# MiniClock.net
KiCad netlist of a schematic drawn in Altium Designer
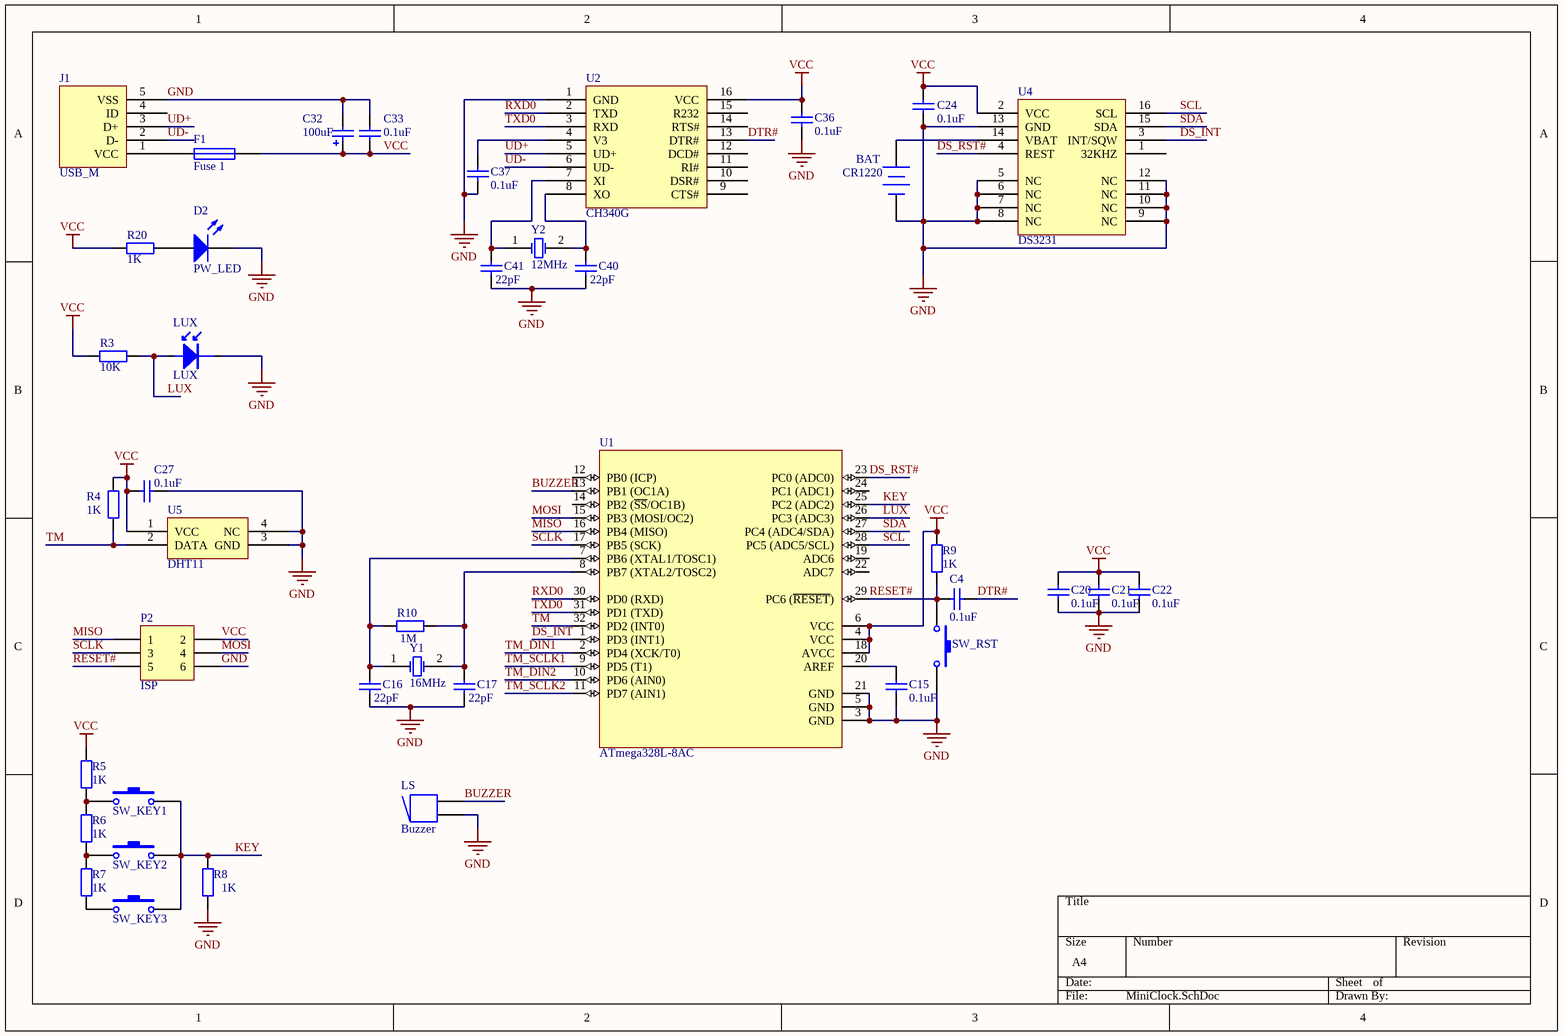
[diagram p0: MiniClock.SchDoc]

(export (version "E")
  (design (tool "Eeschema 10.0.6"))
  (components
    (comp (ref "BAT")
      (value "CR1220")
      (footprint "CR1220")
      (description "Multicell Battery")
      (fields (field (name "PUBLISHER") "Altium Limited"))
      (libsource (lib "Miscellaneous Devices") (part "Battery"))
    )
    (comp (ref "C4")
      (value "0.1uF")
      (footprint "C-0805")
      (description "Capacitor")
      (fields (field (name "Comment") "Cap") (field (name "PUBLISHER") "Altium Limited"))
      (libsource (lib "Miscellaneous Devices") (part "Cap"))
    )
    (comp (ref "C15")
      (value "0.1uF")
      (footprint "C-0805")
      (description "Capacitor")
      (fields (field (name "Comment") "Cap") (field (name "PUBLISHER") "Altium Limited"))
      (libsource (lib "Miscellaneous Devices") (part "Cap"))
    )
    (comp (ref "C16")
      (value "22pF")
      (footprint "C-0805")
      (description "Capacitor")
      (fields (field (name "Comment") "Cap") (field (name "PUBLISHER") "Altium Limited"))
      (libsource (lib "Miscellaneous Devices") (part "Cap"))
    )
    (comp (ref "C17")
      (value "22pF")
      (footprint "C-0805")
      (description "Capacitor")
      (fields (field (name "Comment") "Cap") (field (name "PUBLISHER") "Altium Limited"))
      (libsource (lib "Miscellaneous Devices") (part "Cap"))
    )
    (comp (ref "C20")
      (value "0.1uF")
      (footprint "C-0805")
      (description "Capacitor")
      (fields (field (name "Comment") "Cap") (field (name "PUBLISHER") "Altium Limited"))
      (libsource (lib "Miscellaneous Devices") (part "Cap"))
    )
    (comp (ref "C21")
      (value "0.1uF")
      (footprint "C-0805")
      (description "Capacitor")
      (fields (field (name "Comment") "Cap") (field (name "PUBLISHER") "Altium Limited"))
      (libsource (lib "Miscellaneous Devices") (part "Cap"))
    )
    (comp (ref "C22")
      (value "0.1uF")
      (footprint "C-0805")
      (description "Capacitor")
      (fields (field (name "Comment") "Cap") (field (name "PUBLISHER") "Altium Limited"))
      (libsource (lib "Miscellaneous Devices") (part "Cap"))
    )
    (comp (ref "C24")
      (value "0.1uF")
      (footprint "C-0805")
      (description "Capacitor")
      (fields (field (name "Comment") "Cap") (field (name "PUBLISHER") "Altium Limited"))
      (libsource (lib "Miscellaneous Devices") (part "Cap"))
    )
    (comp (ref "C27")
      (value "0.1uF")
      (footprint "C-0805")
      (description "Capacitor")
      (fields (field (name "Comment") "Cap") (field (name "PUBLISHER") "Altium Limited"))
      (libsource (lib "Miscellaneous Devices") (part "Cap"))
    )
    (comp (ref "C32")
      (value "100uF")
      (footprint "CAP-3528")
      (description "Polarized Capacitor (Axial)")
      (fields (field (name "Comment") "Cap Pol2") (field (name "PUBLISHER") "Altium Limited"))
      (libsource (lib "Miscellaneous Devices") (part "Cap Pol2"))
    )
    (comp (ref "C33")
      (value "0.1uF")
      (footprint "C-0805")
      (description "Capacitor")
      (fields (field (name "Comment") "Cap") (field (name "PUBLISHER") "Altium Limited"))
      (libsource (lib "Miscellaneous Devices") (part "Cap"))
    )
    (comp (ref "C36")
      (value "0.1uF")
      (footprint "C-0805")
      (description "Capacitor")
      (fields (field (name "Comment") "Cap") (field (name "PUBLISHER") "Altium Limited"))
      (libsource (lib "Miscellaneous Devices") (part "Cap"))
    )
    (comp (ref "C37")
      (value "0.1uF")
      (footprint "C-0805")
      (description "Capacitor")
      (fields (field (name "Comment") "Cap") (field (name "PUBLISHER") "Altium Limited"))
      (libsource (lib "Miscellaneous Devices") (part "Cap"))
    )
    (comp (ref "C40")
      (value "22pF")
      (footprint "C-0805")
      (description "Capacitor")
      (fields (field (name "Comment") "Cap") (field (name "PUBLISHER") "Altium Limited"))
      (libsource (lib "Miscellaneous Devices") (part "Cap"))
    )
    (comp (ref "C41")
      (value "22pF")
      (footprint "C-0805")
      (description "Capacitor")
      (fields (field (name "Comment") "Cap") (field (name "PUBLISHER") "Altium Limited"))
      (libsource (lib "Miscellaneous Devices") (part "Cap"))
    )
    (comp (ref "D2")
      (value "PW_LED")
      (footprint "LED-0805")
      (description "Typical RED, GREEN, YELLOW, AMBER GaAs LED")
      (fields (field (name "PUBLISHER") "Altium Limited"))
      (libsource (lib "Miscellaneous Devices") (part "LED2"))
    )
    (comp (ref "F1")
      (value "Fuse 1")
      (footprint "0805-1")
      (description "Fuse")
      (fields (field (name "PUBLISHER") "Altium Limited"))
      (libsource (lib "Miscellaneous Devices") (part "Fuse 1"))
    )
    (comp (ref "J1")
      (value "USB_M")
      (footprint "USB_MICRO_5S_B")
      (description "Micro/Mini USB")
      (libsource (lib "HDR_Fszhang") (part "USB_M"))
    )
    (comp (ref "LS")
      (value "Buzzer")
      (footprint "BEEP-S")
      (description "Magnetic Transducer Buzzer")
      (fields (field (name "PUBLISHER") "Altium Limited"))
      (libsource (lib "Miscellaneous Devices") (part "Buzzer"))
    )
    (comp (ref "LUX") (value "LUX") (footprint "AX_2.54") (libsource (lib "Schlib1") (part "LUX")))
    (comp (ref "P2")
      (value "ISP")
      (footprint "HDR2X3")
      (description "Header, 3-Pin, Dual row")
      (fields (field (name "PUBLISHER") "Altium Limited"))
      (libsource (lib "Miscellaneous Connectors") (part "Header 3X2"))
    )
    (comp (ref "R3")
      (value "10K")
      (footprint "0805-1")
      (description "Resistor")
      (fields (field (name "Comment") "Res2") (field (name "PUBLISHER") "Altium Limited"))
      (libsource (lib "") (part "Res2_3"))
    )
    (comp (ref "R4")
      (value "1K")
      (footprint "0805-1")
      (description "Resistor")
      (fields (field (name "Comment") "Res2") (field (name "PUBLISHER") "Altium Limited"))
      (libsource (lib "Miscellaneous Devices") (part "Res2"))
    )
    (comp (ref "R5")
      (value "1K")
      (footprint "0805-1")
      (description "Resistor")
      (fields (field (name "Comment") "Res2") (field (name "PUBLISHER") "Altium Limited"))
      (libsource (lib "Miscellaneous Devices") (part "Res2"))
    )
    (comp (ref "R6")
      (value "1K")
      (footprint "0805-1")
      (description "Resistor")
      (fields (field (name "Comment") "Res2") (field (name "PUBLISHER") "Altium Limited"))
      (libsource (lib "Miscellaneous Devices") (part "Res2"))
    )
    (comp (ref "R7")
      (value "1K")
      (footprint "0805-1")
      (description "Resistor")
      (fields (field (name "Comment") "Res2") (field (name "PUBLISHER") "Altium Limited"))
      (libsource (lib "Miscellaneous Devices") (part "Res2"))
    )
    (comp (ref "R8")
      (value "1K")
      (footprint "0805-1")
      (description "Resistor")
      (fields (field (name "Comment") "Res2") (field (name "PUBLISHER") "Altium Limited"))
      (libsource (lib "") (part "Res2_2"))
    )
    (comp (ref "R9")
      (value "1K")
      (footprint "0805-1")
      (description "Resistor")
      (fields (field (name "Comment") "Res2") (field (name "PUBLISHER") "Altium Limited"))
      (libsource (lib "Miscellaneous Devices") (part "Res2"))
    )
    (comp (ref "R10")
      (value "1M")
      (footprint "0805-1")
      (description "Resistor")
      (fields (field (name "Comment") "Res2") (field (name "PUBLISHER") "Altium Limited"))
      (libsource (lib "") (part "Res2_1"))
    )
    (comp (ref "R20")
      (value "1K")
      (footprint "0805-1")
      (description "Resistor")
      (fields (field (name "Comment") "Res2") (field (name "PUBLISHER") "Altium Limited"))
      (libsource (lib "") (part "Res2_3"))
    )
    (comp (ref "SW_KEY1")
      (value "SW-PB")
      (footprint "SW_PB2_A1")
      (description "Switch")
      (fields (field (name "PUBLISHER") "Altium Limited"))
      (libsource (lib "Miscellaneous Devices") (part "SW-PB"))
    )
    (comp (ref "SW_KEY2")
      (value "SW-PB")
      (footprint "SW_PB2_A1")
      (description "Switch")
      (fields (field (name "PUBLISHER") "Altium Limited"))
      (libsource (lib "Miscellaneous Devices") (part "SW-PB"))
    )
    (comp (ref "SW_KEY3")
      (value "SW-PB")
      (footprint "SW_PB2_A1")
      (description "Switch")
      (fields (field (name "PUBLISHER") "Altium Limited"))
      (libsource (lib "Miscellaneous Devices") (part "SW-PB"))
    )
    (comp (ref "SW_RST")
      (value "SW-PB")
      (footprint "SW_PB2_A1")
      (description "Switch")
      (fields (field (name "PUBLISHER") "Altium Limited"))
      (libsource (lib "Miscellaneous Devices") (part "SW-PB"))
    )
    (comp (ref "U1")
      (value "ATmega328L-8AC")
      (footprint "32A_M")
      (description "8-Bit AVR Microcontroller with 8K Bytes of In-System Programmable Flash Memory")
      (fields (field (name "PUBLISHER") "Altium Limited"))
      (libsource (lib "Atmel Microcontroller 8-Bit AVR") (part "ATmega8L-8AC"))
    )
    (comp (ref "U2") (value "CH340G") (footprint "SOIC-16") (libsource (lib "Schlib1") (part "CH340G")))
    (comp (ref "U4") (value "DS3231") (footprint "SOIC-16W") (libsource (lib "Schlib1") (part "DS3231")))
    (comp (ref "U5") (value "DHT11") (footprint "DHTxx_simple") (libsource (lib "Schlib1") (part "DHT22")))
    (comp (ref "Y1")
      (value "16MHz")
      (footprint "X-SM49")
      (description "Crystal Oscillator")
      (fields (field (name "PUBLISHER") "Altium Limited"))
      (libsource (lib "Miscellaneous Devices") (part "XTAL"))
    )
    (comp (ref "Y2")
      (value "12MHz")
      (footprint "X-SM49")
      (description "Crystal Oscillator")
      (fields (field (name "PUBLISHER") "Altium Limited"))
      (libsource (lib "Miscellaneous Devices") (part "XTAL"))
    )
  )
  (nets
    (net (code "1") (name "/BUZZER") (class "Default")
      (node (ref "LS") (pin "2") (pinfunction "2_2") (pintype "passive"))
      (node (ref "U1") (pin "13") (pinfunction "PB1_(OC1A)_13") (pintype "bidirectional"))
    )
    (net (code "2") (name "/DS_INT") (class "Default")
      (node (ref "U1") (pin "1") (pinfunction "PD3_(INT1)_1") (pintype "bidirectional"))
      (node (ref "U4") (pin "3") (pinfunction "INT/SQW_3") (pintype "passive"))
    )
    (net (code "3") (name "/DS_RST#") (class "Default")
      (node (ref "U1") (pin "23") (pinfunction "PC0_(ADC0)_23") (pintype "bidirectional"))
      (node (ref "U4") (pin "4") (pinfunction "REST_4") (pintype "passive"))
    )
    (net (code "4") (name "/DTR#") (class "Default")
      (node (ref "C4") (pin "2") (pinfunction "2_2") (pintype "passive"))
      (node (ref "U2") (pin "13") (pinfunction "DTR#_13") (pintype "passive"))
    )
    (net (code "5") (name "/KEY") (class "Default")
      (node (ref "R8") (pin "1") (pinfunction "1_1") (pintype "passive"))
      (node (ref "SW_KEY1") (pin "2") (pinfunction "2_2") (pintype "passive"))
      (node (ref "SW_KEY2") (pin "2") (pinfunction "2_2") (pintype "passive"))
      (node (ref "SW_KEY3") (pin "2") (pinfunction "2_2") (pintype "passive"))
      (node (ref "U1") (pin "25") (pinfunction "PC2_(ADC2)_25") (pintype "bidirectional"))
    )
    (net (code "6") (name "/LUX") (class "Default")
      (node (ref "LUX") (pin "1") (pinfunction "1_1") (pintype "passive"))
      (node (ref "R3") (pin "1") (pinfunction "1_1") (pintype "passive"))
      (node (ref "U1") (pin "26") (pinfunction "PC3_(ADC3)_26") (pintype "bidirectional"))
    )
    (net (code "7") (name "/MISO") (class "Default")
      (node (ref "P2") (pin "1") (pinfunction "1_1") (pintype "passive"))
      (node (ref "U1") (pin "16") (pinfunction "PB4_(MISO)_16") (pintype "bidirectional"))
    )
    (net (code "8") (name "/MOSI") (class "Default")
      (node (ref "P2") (pin "4") (pinfunction "4_4") (pintype "passive"))
      (node (ref "U1") (pin "15") (pinfunction "PB3_(MOSI/OC2)_15") (pintype "bidirectional"))
    )
    (net (code "9") (name "/RESET#") (class "Default")
      (node (ref "C4") (pin "1") (pinfunction "1_1") (pintype "passive"))
      (node (ref "P2") (pin "5") (pinfunction "5_5") (pintype "passive"))
      (node (ref "R9") (pin "1") (pinfunction "1_1") (pintype "passive"))
      (node (ref "SW_RST") (pin "1") (pinfunction "1_1") (pintype "passive"))
      (node (ref "U1") (pin "29") (pinfunction "PC6_(~{RESET})_29") (pintype "bidirectional"))
    )
    (net (code "10") (name "/RXD0") (class "Default")
      (node (ref "U1") (pin "30") (pinfunction "PD0_(RXD)_30") (pintype "bidirectional"))
      (node (ref "U2") (pin "2") (pinfunction "TXD_2") (pintype "passive"))
    )
    (net (code "11") (name "/SCL") (class "Default")
      (node (ref "U1") (pin "28") (pinfunction "PC5_(ADC5/SCL)_28") (pintype "bidirectional"))
      (node (ref "U4") (pin "16") (pinfunction "SCL_16") (pintype "passive"))
    )
    (net (code "12") (name "/SCLK") (class "Default")
      (node (ref "P2") (pin "3") (pinfunction "3_3") (pintype "passive"))
      (node (ref "U1") (pin "17") (pinfunction "PB5_(SCK)_17") (pintype "bidirectional"))
    )
    (net (code "13") (name "/SDA") (class "Default")
      (node (ref "U1") (pin "27") (pinfunction "PC4_(ADC4/SDA)_27") (pintype "bidirectional"))
      (node (ref "U4") (pin "15") (pinfunction "SDA_15") (pintype "passive"))
    )
    (net (code "14") (name "/TM") (class "Default")
      (node (ref "R4") (pin "1") (pinfunction "1_1") (pintype "passive"))
      (node (ref "U1") (pin "32") (pinfunction "PD2_(INT0)_32") (pintype "bidirectional"))
      (node (ref "U5") (pin "2") (pinfunction "DATA_2") (pintype "passive"))
    )
    (net (code "15") (name "/TM_DIN1") (class "Default")
      (node (ref "U1") (pin "2") (pinfunction "PD4_(XCK/T0)_2") (pintype "bidirectional"))
    )
    (net (code "16") (name "/TM_DIN2") (class "Default")
      (node (ref "U1") (pin "10") (pinfunction "PD6_(AIN0)_10") (pintype "bidirectional"))
    )
    (net (code "17") (name "/TM_SCLK1") (class "Default")
      (node (ref "U1") (pin "9") (pinfunction "PD5_(T1)_9") (pintype "bidirectional"))
    )
    (net (code "18") (name "/TM_SCLK2") (class "Default")
      (node (ref "U1") (pin "11") (pinfunction "PD7_(AIN1)_11") (pintype "bidirectional"))
    )
    (net (code "19") (name "/TXD0") (class "Default")
      (node (ref "U1") (pin "31") (pinfunction "PD1_(TXD)_31") (pintype "bidirectional"))
      (node (ref "U2") (pin "3") (pinfunction "RXD_3") (pintype "passive"))
    )
    (net (code "20") (name "/UD+") (class "Default")
      (node (ref "J1") (pin "3") (pinfunction "D+_3") (pintype "passive"))
      (node (ref "U2") (pin "5") (pinfunction "UD+_5") (pintype "passive"))
    )
    (net (code "21") (name "/UD-") (class "Default")
      (node (ref "J1") (pin "2") (pinfunction "D-_2") (pintype "passive"))
      (node (ref "U2") (pin "6") (pinfunction "UD-_6") (pintype "passive"))
    )
    (net (code "22") (name "GND") (class "Default")
      (node (ref "BAT") (pin "2") (pinfunction "-_2") (pintype "passive"))
      (node (ref "C15") (pin "1") (pinfunction "1_1") (pintype "passive"))
      (node (ref "C16") (pin "1") (pinfunction "1_1") (pintype "passive"))
      (node (ref "C17") (pin "1") (pinfunction "1_1") (pintype "passive"))
      (node (ref "C20") (pin "1") (pinfunction "1_1") (pintype "passive"))
      (node (ref "C21") (pin "1") (pinfunction "1_1") (pintype "passive"))
      (node (ref "C22") (pin "1") (pinfunction "1_1") (pintype "passive"))
      (node (ref "C24") (pin "1") (pinfunction "1_1") (pintype "passive"))
      (node (ref "C27") (pin "1") (pinfunction "1_1") (pintype "passive"))
      (node (ref "C32") (pin "2") (pinfunction "2_2") (pintype "passive"))
      (node (ref "C33") (pin "2") (pinfunction "2_2") (pintype "passive"))
      (node (ref "C36") (pin "1") (pinfunction "1_1") (pintype "passive"))
      (node (ref "C37") (pin "1") (pinfunction "1_1") (pintype "passive"))
      (node (ref "C40") (pin "1") (pinfunction "1_1") (pintype "passive"))
      (node (ref "C41") (pin "1") (pinfunction "1_1") (pintype "passive"))
      (node (ref "D2") (pin "2") (pinfunction "K_2") (pintype "passive"))
      (node (ref "J1") (pin "5") (pinfunction "VSS_5") (pintype "passive"))
      (node (ref "LS") (pin "1") (pinfunction "1_1") (pintype "passive"))
      (node (ref "LUX") (pin "2") (pinfunction "2_2") (pintype "passive"))
      (node (ref "P2") (pin "6") (pinfunction "6_6") (pintype "passive"))
      (node (ref "R8") (pin "2") (pinfunction "2_2") (pintype "passive"))
      (node (ref "SW_RST") (pin "2") (pinfunction "2_2") (pintype "passive"))
      (node (ref "U1") (pin "21") (pinfunction "GND_21") (pintype "power_in"))
      (node (ref "U1") (pin "3") (pinfunction "GND_3") (pintype "power_in"))
      (node (ref "U1") (pin "5") (pinfunction "GND_5") (pintype "power_in"))
      (node (ref "U2") (pin "1") (pinfunction "GND_1") (pintype "passive"))
      (node (ref "U4") (pin "10") (pinfunction "NC_10") (pintype "passive"))
      (node (ref "U4") (pin "11") (pinfunction "NC_11") (pintype "passive"))
      (node (ref "U4") (pin "12") (pinfunction "NC_12") (pintype "passive"))
      (node (ref "U4") (pin "13") (pinfunction "GND_13") (pintype "passive"))
      (node (ref "U4") (pin "5") (pinfunction "NC_5") (pintype "passive"))
      (node (ref "U4") (pin "6") (pinfunction "NC_6") (pintype "passive"))
      (node (ref "U4") (pin "7") (pinfunction "NC_7") (pintype "passive"))
      (node (ref "U4") (pin "8") (pinfunction "NC_8") (pintype "passive"))
      (node (ref "U4") (pin "9") (pinfunction "NC_9") (pintype "passive"))
      (node (ref "U5") (pin "3") (pinfunction "GND_3") (pintype "passive"))
      (node (ref "U5") (pin "4") (pinfunction "NC_4") (pintype "passive"))
    )
    (net (code "23") (name "Net-(BAT-+)") (class "Default")
      (node (ref "BAT") (pin "1") (pinfunction "+_1") (pintype "passive"))
      (node (ref "U4") (pin "14") (pinfunction "VBAT_14") (pintype "passive"))
    )
    (net (code "24") (name "Net-(D2-A)") (class "Default")
      (node (ref "D2") (pin "1") (pinfunction "A_1") (pintype "passive"))
      (node (ref "R20") (pin "1") (pinfunction "1_1") (pintype "passive"))
    )
    (net (code "25") (name "Net-(J1-VCC)") (class "Default")
      (node (ref "F1") (pin "1") (pinfunction "1_1") (pintype "passive"))
      (node (ref "J1") (pin "1") (pinfunction "VCC_1") (pintype "passive"))
    )
    (net (code "26") (name "Net-(R5-Pad1)") (class "Default")
      (node (ref "R5") (pin "1") (pinfunction "1_1") (pintype "passive"))
      (node (ref "R6") (pin "2") (pinfunction "2_2") (pintype "passive"))
      (node (ref "SW_KEY1") (pin "1") (pinfunction "1_1") (pintype "passive"))
    )
    (net (code "27") (name "Net-(R6-Pad1)") (class "Default")
      (node (ref "R6") (pin "1") (pinfunction "1_1") (pintype "passive"))
      (node (ref "R7") (pin "2") (pinfunction "2_2") (pintype "passive"))
      (node (ref "SW_KEY2") (pin "1") (pinfunction "1_1") (pintype "passive"))
    )
    (net (code "28") (name "Net-(R7-Pad1)") (class "Default")
      (node (ref "R7") (pin "1") (pinfunction "1_1") (pintype "passive"))
      (node (ref "SW_KEY3") (pin "1") (pinfunction "1_1") (pintype "passive"))
    )
    (net (code "29") (name "Net-(U1-AREF)") (class "Default")
      (node (ref "C15") (pin "2") (pinfunction "2_2") (pintype "passive"))
      (node (ref "U1") (pin "20") (pinfunction "AREF_20") (pintype "passive"))
    )
    (net (code "30") (name "Net-(U1-PB6_(XTAL1{slash}TOSC1))") (class "Default")
      (node (ref "C16") (pin "2") (pinfunction "2_2") (pintype "passive"))
      (node (ref "R10") (pin "1") (pinfunction "1_1") (pintype "passive"))
      (node (ref "U1") (pin "7") (pinfunction "PB6_(XTAL1/TOSC1)_7") (pintype "bidirectional"))
      (node (ref "Y1") (pin "1") (pinfunction "OSC1_1") (pintype "passive"))
    )
    (net (code "31") (name "Net-(U1-PB7_(XTAL2{slash}TOSC2))") (class "Default")
      (node (ref "C17") (pin "2") (pinfunction "2_2") (pintype "passive"))
      (node (ref "R10") (pin "2") (pinfunction "2_2") (pintype "passive"))
      (node (ref "U1") (pin "8") (pinfunction "PB7_(XTAL2/TOSC2)_8") (pintype "bidirectional"))
      (node (ref "Y1") (pin "2") (pinfunction "OSC2_2") (pintype "passive"))
    )
    (net (code "32") (name "Net-(U2-V3)") (class "Default")
      (node (ref "C37") (pin "2") (pinfunction "2_2") (pintype "passive"))
      (node (ref "U2") (pin "4") (pinfunction "V3_4") (pintype "passive"))
    )
    (net (code "33") (name "Net-(U2-XI)") (class "Default")
      (node (ref "C41") (pin "2") (pinfunction "2_2") (pintype "passive"))
      (node (ref "U2") (pin "7") (pinfunction "XI_7") (pintype "passive"))
      (node (ref "Y2") (pin "1") (pinfunction "OSC1_1") (pintype "passive"))
    )
    (net (code "34") (name "Net-(U2-XO)") (class "Default")
      (node (ref "C40") (pin "2") (pinfunction "2_2") (pintype "passive"))
      (node (ref "U2") (pin "8") (pinfunction "XO_8") (pintype "passive"))
      (node (ref "Y2") (pin "2") (pinfunction "OSC2_2") (pintype "passive"))
    )
    (net (code "35") (name "VCC") (class "Default")
      (node (ref "C20") (pin "2") (pinfunction "2_2") (pintype "passive"))
      (node (ref "C21") (pin "2") (pinfunction "2_2") (pintype "passive"))
      (node (ref "C22") (pin "2") (pinfunction "2_2") (pintype "passive"))
      (node (ref "C24") (pin "2") (pinfunction "2_2") (pintype "passive"))
      (node (ref "C27") (pin "2") (pinfunction "2_2") (pintype "passive"))
      (node (ref "C32") (pin "1") (pinfunction "1_1") (pintype "passive"))
      (node (ref "C33") (pin "1") (pinfunction "1_1") (pintype "passive"))
      (node (ref "C36") (pin "2") (pinfunction "2_2") (pintype "passive"))
      (node (ref "F1") (pin "2") (pinfunction "2_2") (pintype "passive"))
      (node (ref "P2") (pin "2") (pinfunction "2_2") (pintype "passive"))
      (node (ref "R20") (pin "2") (pinfunction "2_2") (pintype "passive"))
      (node (ref "R3") (pin "2") (pinfunction "2_2") (pintype "passive"))
      (node (ref "R4") (pin "2") (pinfunction "2_2") (pintype "passive"))
      (node (ref "R5") (pin "2") (pinfunction "2_2") (pintype "passive"))
      (node (ref "R9") (pin "2") (pinfunction "2_2") (pintype "passive"))
      (node (ref "U1") (pin "18") (pinfunction "AVCC_18") (pintype "power_in"))
      (node (ref "U1") (pin "4") (pinfunction "VCC_4") (pintype "power_in"))
      (node (ref "U1") (pin "6") (pinfunction "VCC_6") (pintype "power_in"))
      (node (ref "U2") (pin "16") (pinfunction "VCC_16") (pintype "passive"))
      (node (ref "U4") (pin "2") (pinfunction "VCC_2") (pintype "passive"))
      (node (ref "U5") (pin "1") (pinfunction "VCC_1") (pintype "passive"))
    )
    (net (code "36") (name "unconnected-(J1-ID-Pad4)") (class "Default")
      (node (ref "J1") (pin "4") (pinfunction "ID_4") (pintype "passive"))
    )
    (net (code "37") (name "unconnected-(U1-ADC6-Pad19)") (class "Default")
      (node (ref "U1") (pin "19") (pinfunction "ADC6_19") (pintype "bidirectional"))
    )
    (net (code "38") (name "unconnected-(U1-ADC7-Pad22)") (class "Default")
      (node (ref "U1") (pin "22") (pinfunction "ADC7_22") (pintype "bidirectional"))
    )
    (net (code "39") (name "unconnected-(U1-PB0_(ICP)-Pad12)") (class "Default")
      (node (ref "U1") (pin "12") (pinfunction "PB0_(ICP)_12") (pintype "bidirectional"))
    )
    (net (code "40") (name "unconnected-(U1-PB2_(~{SS}{slash}OC1B)-Pad14)") (class "Default")
      (node (ref "U1") (pin "14") (pinfunction "PB2_(~{SS}/OC1B)_14") (pintype "bidirectional"))
    )
    (net (code "41") (name "unconnected-(U1-PC1_(ADC1)-Pad24)") (class "Default")
      (node (ref "U1") (pin "24") (pinfunction "PC1_(ADC1)_24") (pintype "bidirectional"))
    )
    (net (code "42") (name "unconnected-(U2-CTS#-Pad9)") (class "Default")
      (node (ref "U2") (pin "9") (pinfunction "CTS#_9") (pintype "passive"))
    )
    (net (code "43") (name "unconnected-(U2-DCD#-Pad12)") (class "Default")
      (node (ref "U2") (pin "12") (pinfunction "DCD#_12") (pintype "passive"))
    )
    (net (code "44") (name "unconnected-(U2-DSR#-Pad10)") (class "Default")
      (node (ref "U2") (pin "10") (pinfunction "DSR#_10") (pintype "passive"))
    )
    (net (code "45") (name "unconnected-(U2-R232-Pad15)") (class "Default")
      (node (ref "U2") (pin "15") (pinfunction "R232_15") (pintype "passive"))
    )
    (net (code "46") (name "unconnected-(U2-RI#-Pad11)") (class "Default")
      (node (ref "U2") (pin "11") (pinfunction "RI#_11") (pintype "passive"))
    )
    (net (code "47") (name "unconnected-(U2-RTS#-Pad14)") (class "Default")
      (node (ref "U2") (pin "14") (pinfunction "RTS#_14") (pintype "passive"))
    )
    (net (code "48") (name "unconnected-(U4-32KHZ-Pad1)") (class "Default")
      (node (ref "U4") (pin "1") (pinfunction "32KHZ_1") (pintype "passive"))
    )
  )
)
